# snc98_Display_15x7-Segment_3-digitDispla.net
KiCad netlist of a schematic drawn in EAGLE
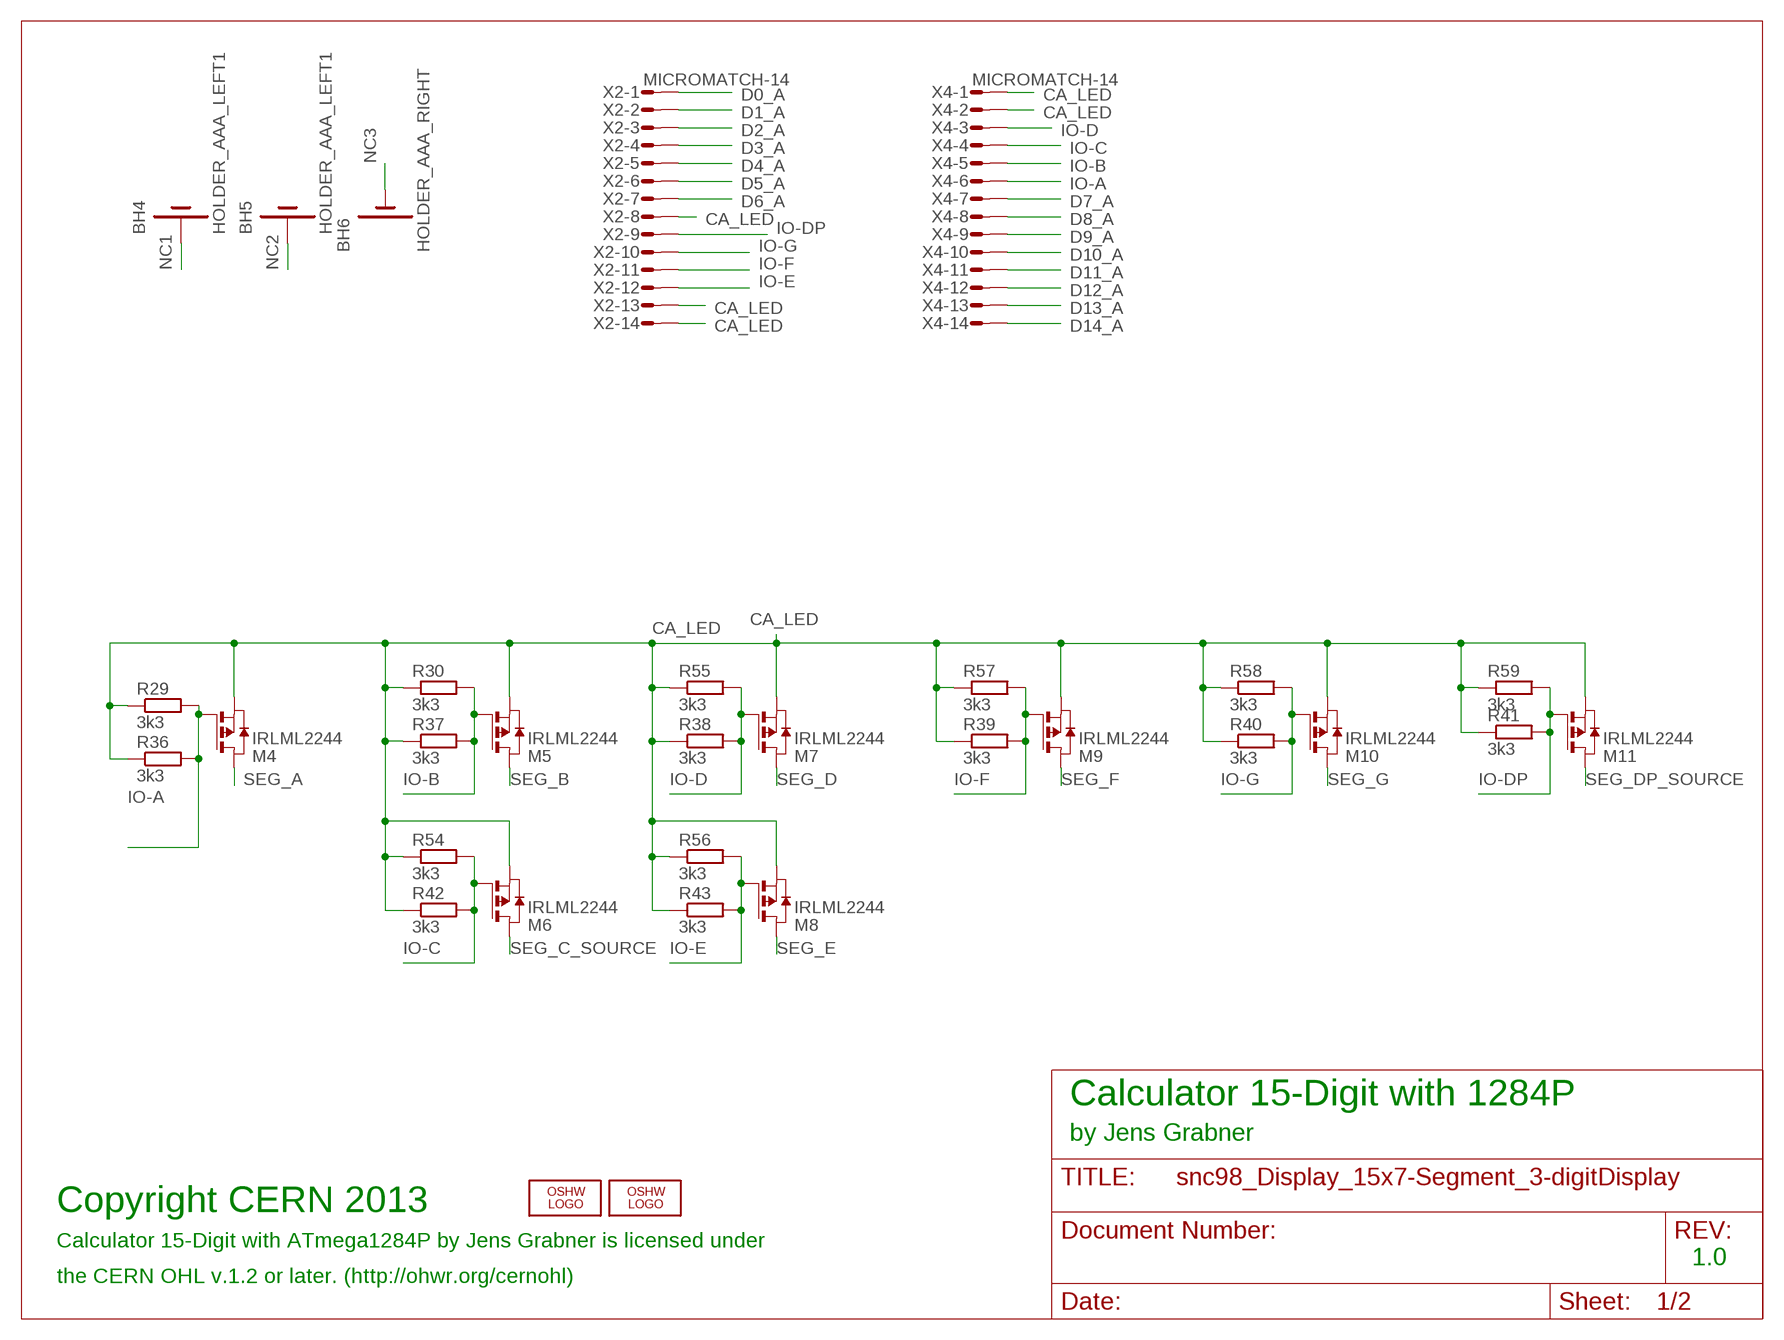
[diagram p0: schematic, sheet 1]
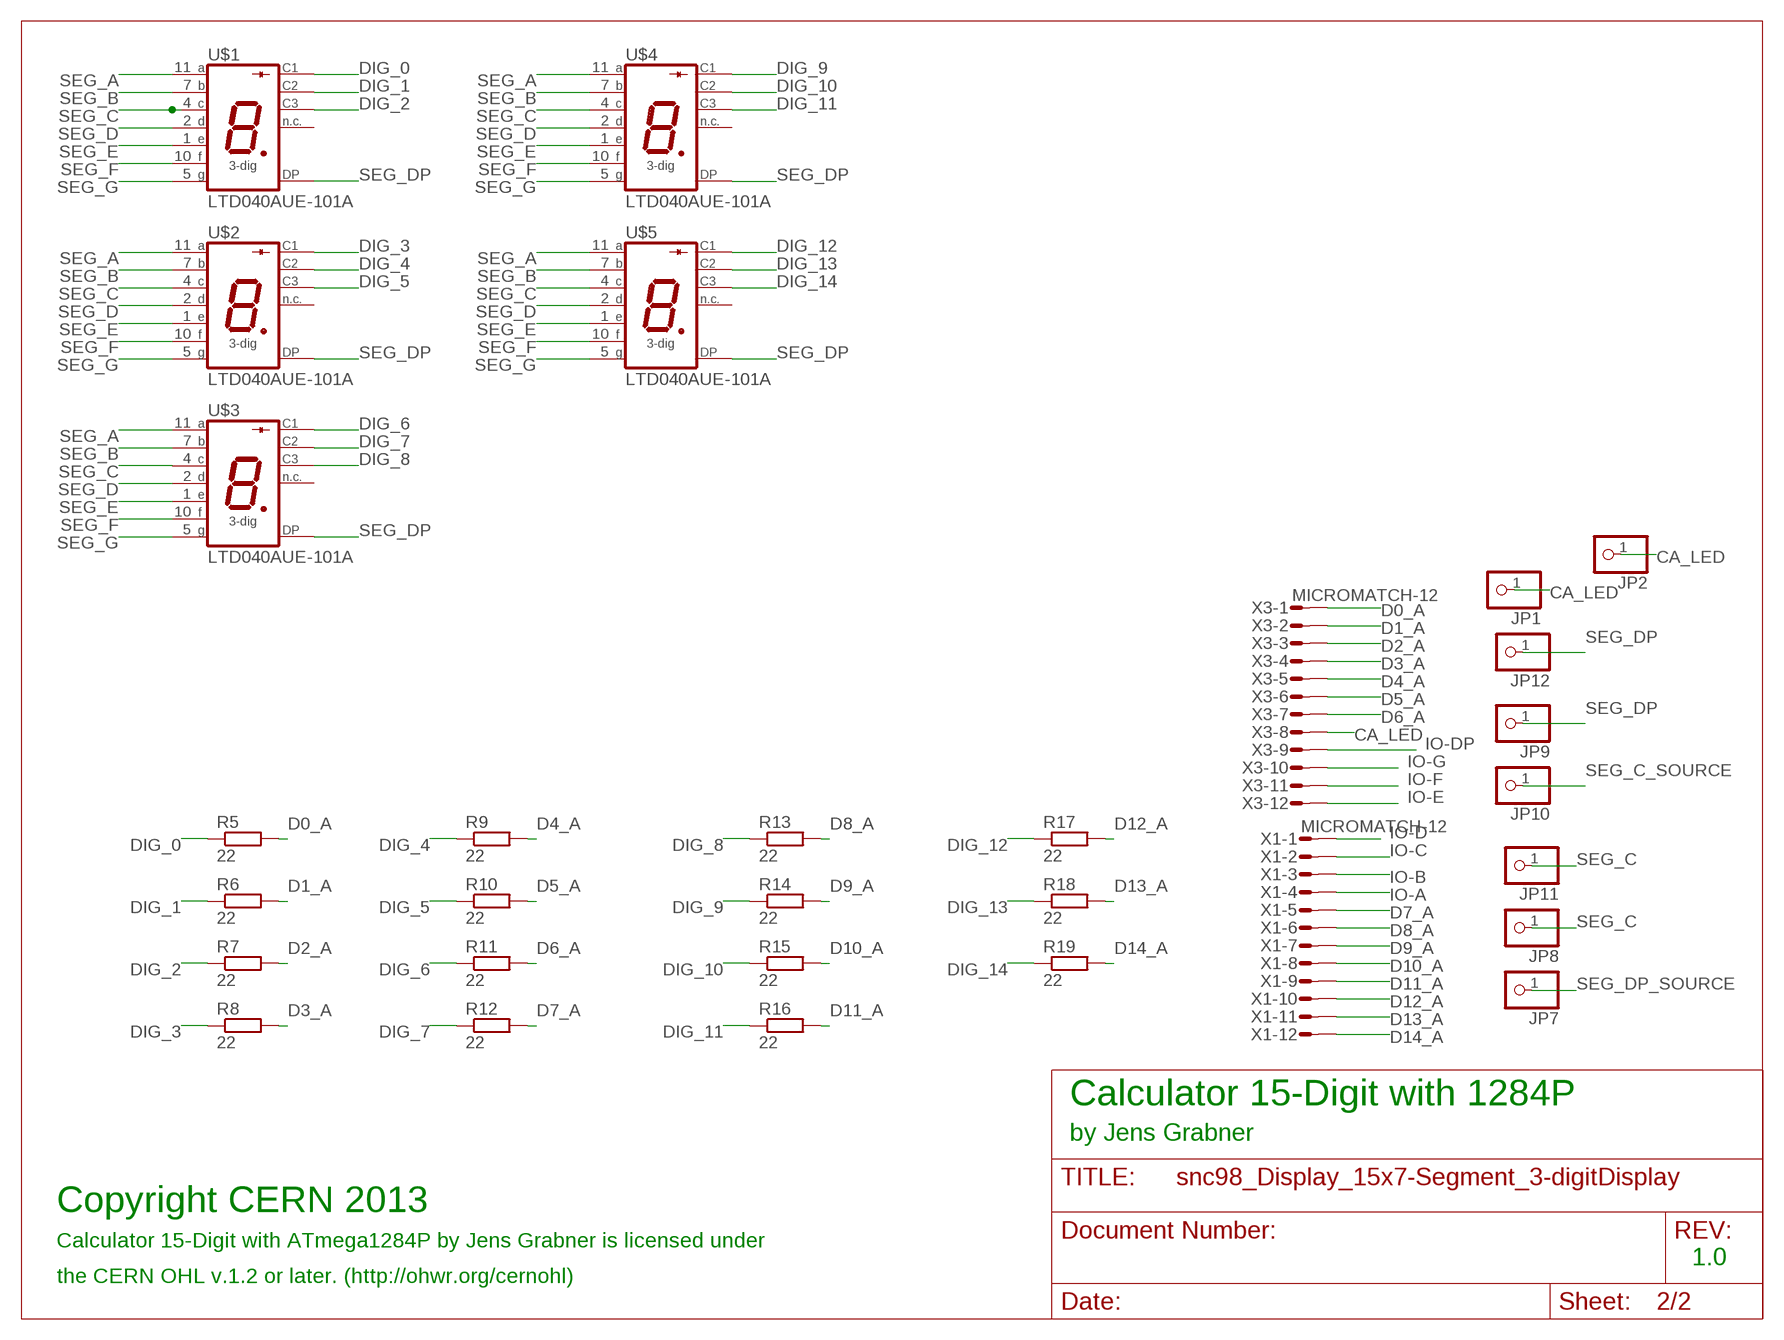
[diagram p1: schematic, sheet 2]

(export (version "E")
  (design (tool "Eeschema 10.0.6"))
  (components
    (comp (ref "JP1")
      (value "PINHD-1X1")
      (footprint "eagle-import:1X01")
      (libsource (lib "eagle-import") (part "PINHD-1X1"))
    )
    (comp (ref "JP2")
      (value "PINHD-1X1")
      (footprint "eagle-import:1X01")
      (libsource (lib "eagle-import") (part "PINHD-1X1"))
    )
    (comp (ref "JP7")
      (value "PINHD-1X1")
      (footprint "eagle-import:1X01")
      (libsource (lib "eagle-import") (part "PINHD-1X1"))
    )
    (comp (ref "JP8")
      (value "PINHD-1X1")
      (footprint "eagle-import:1X01")
      (libsource (lib "eagle-import") (part "PINHD-1X1"))
    )
    (comp (ref "JP9")
      (value "PINHD-1X1")
      (footprint "eagle-import:1X01")
      (libsource (lib "eagle-import") (part "PINHD-1X1"))
    )
    (comp (ref "JP10")
      (value "PINHD-1X1")
      (footprint "eagle-import:1X01")
      (libsource (lib "eagle-import") (part "PINHD-1X1"))
    )
    (comp (ref "JP11")
      (value "PINHD-1X1")
      (footprint "eagle-import:1X01")
      (libsource (lib "eagle-import") (part "PINHD-1X1"))
    )
    (comp (ref "JP12")
      (value "PINHD-1X1")
      (footprint "eagle-import:1X01")
      (libsource (lib "eagle-import") (part "PINHD-1X1"))
    )
    (comp (ref "R5")
      (value "22")
      (footprint "eagle-import:R1210")
      (libsource (lib "eagle-import") (part "R-EU_R1210"))
    )
    (comp (ref "R6")
      (value "22")
      (footprint "eagle-import:R1210")
      (libsource (lib "eagle-import") (part "R-EU_R1210"))
    )
    (comp (ref "R7")
      (value "22")
      (footprint "eagle-import:R1210")
      (libsource (lib "eagle-import") (part "R-EU_R1210"))
    )
    (comp (ref "R8")
      (value "22")
      (footprint "eagle-import:R1210")
      (libsource (lib "eagle-import") (part "R-EU_R1210"))
    )
    (comp (ref "R9")
      (value "22")
      (footprint "eagle-import:R1210")
      (libsource (lib "eagle-import") (part "R-EU_R1210"))
    )
    (comp (ref "R10")
      (value "22")
      (footprint "eagle-import:R1210")
      (libsource (lib "eagle-import") (part "R-EU_R1210"))
    )
    (comp (ref "R11")
      (value "22")
      (footprint "eagle-import:R1210")
      (libsource (lib "eagle-import") (part "R-EU_R1210"))
    )
    (comp (ref "R12")
      (value "22")
      (footprint "eagle-import:R1210")
      (libsource (lib "eagle-import") (part "R-EU_R1210"))
    )
    (comp (ref "R13")
      (value "22")
      (footprint "eagle-import:R1210")
      (libsource (lib "eagle-import") (part "R-EU_R1210"))
    )
    (comp (ref "R14")
      (value "22")
      (footprint "eagle-import:R1210")
      (libsource (lib "eagle-import") (part "R-EU_R1210"))
    )
    (comp (ref "R15")
      (value "22")
      (footprint "eagle-import:R1210")
      (libsource (lib "eagle-import") (part "R-EU_R1210"))
    )
    (comp (ref "R16")
      (value "22")
      (footprint "eagle-import:R1210")
      (libsource (lib "eagle-import") (part "R-EU_R1210"))
    )
    (comp (ref "R17")
      (value "22")
      (footprint "eagle-import:R1210")
      (libsource (lib "eagle-import") (part "R-EU_R1210"))
    )
    (comp (ref "R18")
      (value "22")
      (footprint "eagle-import:R1210")
      (libsource (lib "eagle-import") (part "R-EU_R1210"))
    )
    (comp (ref "R19")
      (value "22")
      (footprint "eagle-import:R1210")
      (libsource (lib "eagle-import") (part "R-EU_R1210"))
    )
    (comp (ref "U$1")
      (value "LTD040AUE-101A")
      (footprint "eagle-import:LTD040AUE-101A")
      (libsource (lib "eagle-import") (part "LTD040AUE-101A"))
    )
    (comp (ref "U$2")
      (value "LTD040AUE-101A")
      (footprint "eagle-import:LTD040AUE-101A")
      (libsource (lib "eagle-import") (part "LTD040AUE-101A"))
    )
    (comp (ref "U$3")
      (value "LTD040AUE-101A")
      (footprint "eagle-import:LTD040AUE-101A")
      (libsource (lib "eagle-import") (part "LTD040AUE-101A"))
    )
    (comp (ref "U$4")
      (value "LTD040AUE-101A")
      (footprint "eagle-import:LTD040AUE-101A")
      (libsource (lib "eagle-import") (part "LTD040AUE-101A"))
    )
    (comp (ref "U$5")
      (value "LTD040AUE-101A")
      (footprint "eagle-import:LTD040AUE-101A")
      (libsource (lib "eagle-import") (part "LTD040AUE-101A"))
    )
    (comp (ref "X1")
      (value "MICROMATCH-12")
      (footprint "eagle-import:MICROMATCH-12")
      (fields (field (name "MF") "FARNELL") (field (name "MPN") "8-215464-2"))
      (libsource (lib "eagle-import") (part "MICROMATCH-12"))
    )
    (comp (ref "X3")
      (value "MICROMATCH-12")
      (footprint "eagle-import:MICROMATCH-12")
      (fields (field (name "MF") "FARNELL") (field (name "MPN") "8-215464-2"))
      (libsource (lib "eagle-import") (part "MICROMATCH-12"))
    )
    (comp (ref "BH4")
      (value "HOLDER_AAA_LEFT1")
      (footprint "eagle-import:BATTERY-AAA-LEFT")
      (libsource (lib "eagle-import") (part "HOLDER_AAA_LEFT1"))
    )
    (comp (ref "BH5")
      (value "HOLDER_AAA_LEFT1")
      (footprint "eagle-import:BATTERY-AAA-LEFT")
      (libsource (lib "eagle-import") (part "HOLDER_AAA_LEFT1"))
    )
    (comp (ref "BH6")
      (value "HOLDER_AAA_RIGHT")
      (footprint "eagle-import:BATTERY-AAA-RIGHT")
      (libsource (lib "eagle-import") (part "HOLDER_AAA_RIGHT"))
    )
    (comp (ref "LOGO1")
      (value "OSHW_LOGO_8MILX0150-NT")
      (footprint "eagle-import:OSHW_8X150_NOTEXT")
      (libsource (lib "eagle-import") (part "OSHW_LOGO_8MILX0150-NT"))
    )
    (comp (ref "LOGO3")
      (value "OSHW_LOGO_6MILX0100-NT")
      (footprint "eagle-import:OSHW_6X100_NOTEXT")
      (libsource (lib "eagle-import") (part "OSHW_LOGO_6MILX0100-NT"))
    )
    (comp (ref "M4")
      (value "IRLML2244")
      (footprint "eagle-import:SOT-23")
      (libsource (lib "eagle-import") (part "IRLML6402"))
    )
    (comp (ref "M5")
      (value "IRLML2244")
      (footprint "eagle-import:SOT-23")
      (libsource (lib "eagle-import") (part "IRLML6402"))
    )
    (comp (ref "M6")
      (value "IRLML2244")
      (footprint "eagle-import:SOT-23")
      (libsource (lib "eagle-import") (part "IRLML6402"))
    )
    (comp (ref "M7")
      (value "IRLML2244")
      (footprint "eagle-import:SOT-23")
      (libsource (lib "eagle-import") (part "IRLML6402"))
    )
    (comp (ref "M8")
      (value "IRLML2244")
      (footprint "eagle-import:SOT-23")
      (libsource (lib "eagle-import") (part "IRLML6402"))
    )
    (comp (ref "M9")
      (value "IRLML2244")
      (footprint "eagle-import:SOT-23")
      (libsource (lib "eagle-import") (part "IRLML6402"))
    )
    (comp (ref "M10")
      (value "IRLML2244")
      (footprint "eagle-import:SOT-23")
      (libsource (lib "eagle-import") (part "IRLML6402"))
    )
    (comp (ref "M11")
      (value "IRLML2244")
      (footprint "eagle-import:SOT-23")
      (libsource (lib "eagle-import") (part "IRLML6402"))
    )
    (comp (ref "R29")
      (value "3k3")
      (footprint "eagle-import:0204_5")
      (libsource (lib "eagle-import") (part "R-EU_0204/5"))
    )
    (comp (ref "R30")
      (value "3k3")
      (footprint "eagle-import:0204_5")
      (libsource (lib "eagle-import") (part "R-EU_0204/5"))
    )
    (comp (ref "R36")
      (value "3k3")
      (footprint "eagle-import:R1206")
      (libsource (lib "eagle-import") (part "R-EU_R1206"))
    )
    (comp (ref "R37")
      (value "3k3")
      (footprint "eagle-import:R1206")
      (libsource (lib "eagle-import") (part "R-EU_R1206"))
    )
    (comp (ref "R38")
      (value "3k3")
      (footprint "eagle-import:R1206")
      (libsource (lib "eagle-import") (part "R-EU_R1206"))
    )
    (comp (ref "R39")
      (value "3k3")
      (footprint "eagle-import:R1206")
      (libsource (lib "eagle-import") (part "R-EU_R1206"))
    )
    (comp (ref "R40")
      (value "3k3")
      (footprint "eagle-import:R1206")
      (libsource (lib "eagle-import") (part "R-EU_R1206"))
    )
    (comp (ref "R41")
      (value "3k3")
      (footprint "eagle-import:R1206")
      (libsource (lib "eagle-import") (part "R-EU_R1206"))
    )
    (comp (ref "R42")
      (value "3k3")
      (footprint "eagle-import:R1206")
      (libsource (lib "eagle-import") (part "R-EU_R1206"))
    )
    (comp (ref "R43")
      (value "3k3")
      (footprint "eagle-import:R1206")
      (libsource (lib "eagle-import") (part "R-EU_R1206"))
    )
    (comp (ref "R54")
      (value "3k3")
      (footprint "eagle-import:0204_5")
      (libsource (lib "eagle-import") (part "R-EU_0204/5"))
    )
    (comp (ref "R55")
      (value "3k3")
      (footprint "eagle-import:0204_5")
      (libsource (lib "eagle-import") (part "R-EU_0204/5"))
    )
    (comp (ref "R56")
      (value "3k3")
      (footprint "eagle-import:0204_5")
      (libsource (lib "eagle-import") (part "R-EU_0204/5"))
    )
    (comp (ref "R57")
      (value "3k3")
      (footprint "eagle-import:0204_5")
      (libsource (lib "eagle-import") (part "R-EU_0204/5"))
    )
    (comp (ref "R58")
      (value "3k3")
      (footprint "eagle-import:0204_5")
      (libsource (lib "eagle-import") (part "R-EU_0204/5"))
    )
    (comp (ref "R59")
      (value "3k3")
      (footprint "eagle-import:0204_5")
      (libsource (lib "eagle-import") (part "R-EU_0204/5"))
    )
    (comp (ref "X2")
      (value "MICROMATCH-14")
      (footprint "eagle-import:MICROMATCH-14")
      (fields (field (name "MF") "FARNELL") (field (name "MPN") "8-215464-4"))
      (libsource (lib "eagle-import") (part "MICROMATCH-14"))
    )
    (comp (ref "X4")
      (value "MICROMATCH-14")
      (footprint "eagle-import:MICROMATCH-14")
      (fields (field (name "MF") "FARNELL") (field (name "MPN") "8-215464-4"))
      (libsource (lib "eagle-import") (part "MICROMATCH-14"))
    )
  )
  (nets
    (net (code "1") (name "CA_LED") (class "Default")
      (node (ref "JP1") (pin "1") (pinfunction "1_1") (pintype "passive"))
      (node (ref "JP2") (pin "1") (pinfunction "1_1") (pintype "passive"))
      (node (ref "M10") (pin "2") (pinfunction "S_2") (pintype "passive"))
      (node (ref "M11") (pin "2") (pinfunction "S_2") (pintype "passive"))
      (node (ref "M4") (pin "2") (pinfunction "S_2") (pintype "passive"))
      (node (ref "M5") (pin "2") (pinfunction "S_2") (pintype "passive"))
      (node (ref "M6") (pin "2") (pinfunction "S_2") (pintype "passive"))
      (node (ref "M7") (pin "2") (pinfunction "S_2") (pintype "passive"))
      (node (ref "M8") (pin "2") (pinfunction "S_2") (pintype "passive"))
      (node (ref "M9") (pin "2") (pinfunction "S_2") (pintype "passive"))
      (node (ref "R29") (pin "1") (pinfunction "1_1") (pintype "passive"))
      (node (ref "R30") (pin "1") (pinfunction "1_1") (pintype "passive"))
      (node (ref "R36") (pin "1") (pinfunction "1_1") (pintype "passive"))
      (node (ref "R37") (pin "1") (pinfunction "1_1") (pintype "passive"))
      (node (ref "R38") (pin "1") (pinfunction "1_1") (pintype "passive"))
      (node (ref "R39") (pin "1") (pinfunction "1_1") (pintype "passive"))
      (node (ref "R40") (pin "1") (pinfunction "1_1") (pintype "passive"))
      (node (ref "R41") (pin "1") (pinfunction "1_1") (pintype "passive"))
      (node (ref "R42") (pin "1") (pinfunction "1_1") (pintype "passive"))
      (node (ref "R43") (pin "1") (pinfunction "1_1") (pintype "passive"))
      (node (ref "R54") (pin "1") (pinfunction "1_1") (pintype "passive"))
      (node (ref "R55") (pin "1") (pinfunction "1_1") (pintype "passive"))
      (node (ref "R56") (pin "1") (pinfunction "1_1") (pintype "passive"))
      (node (ref "R57") (pin "1") (pinfunction "1_1") (pintype "passive"))
      (node (ref "R58") (pin "1") (pinfunction "1_1") (pintype "passive"))
      (node (ref "R59") (pin "1") (pinfunction "1_1") (pintype "passive"))
      (node (ref "X2") (pin "13") (pinfunction "S_13") (pintype "passive"))
      (node (ref "X2") (pin "14") (pinfunction "S_14") (pintype "passive"))
      (node (ref "X2") (pin "8") (pinfunction "S_8") (pintype "passive"))
      (node (ref "X3") (pin "8") (pinfunction "S_8") (pintype "passive"))
      (node (ref "X4") (pin "1") (pinfunction "S_1") (pintype "passive"))
      (node (ref "X4") (pin "2") (pinfunction "S_2") (pintype "passive"))
    )
    (net (code "2") (name "D0_A") (class "Default")
      (node (ref "R5") (pin "2") (pinfunction "2_2") (pintype "passive"))
      (node (ref "X2") (pin "1") (pinfunction "S_1") (pintype "passive"))
      (node (ref "X3") (pin "1") (pinfunction "S_1") (pintype "passive"))
    )
    (net (code "3") (name "D1_A") (class "Default")
      (node (ref "R6") (pin "2") (pinfunction "2_2") (pintype "passive"))
      (node (ref "X2") (pin "2") (pinfunction "S_2") (pintype "passive"))
      (node (ref "X3") (pin "2") (pinfunction "S_2") (pintype "passive"))
    )
    (net (code "4") (name "D2_A") (class "Default")
      (node (ref "R7") (pin "2") (pinfunction "2_2") (pintype "passive"))
      (node (ref "X2") (pin "3") (pinfunction "S_3") (pintype "passive"))
      (node (ref "X3") (pin "3") (pinfunction "S_3") (pintype "passive"))
    )
    (net (code "5") (name "D3_A") (class "Default")
      (node (ref "R8") (pin "2") (pinfunction "2_2") (pintype "passive"))
      (node (ref "X2") (pin "4") (pinfunction "S_4") (pintype "passive"))
      (node (ref "X3") (pin "4") (pinfunction "S_4") (pintype "passive"))
    )
    (net (code "6") (name "D4_A") (class "Default")
      (node (ref "R9") (pin "2") (pinfunction "2_2") (pintype "passive"))
      (node (ref "X2") (pin "5") (pinfunction "S_5") (pintype "passive"))
      (node (ref "X3") (pin "5") (pinfunction "S_5") (pintype "passive"))
    )
    (net (code "7") (name "D5_A") (class "Default")
      (node (ref "R10") (pin "2") (pinfunction "2_2") (pintype "passive"))
      (node (ref "X2") (pin "6") (pinfunction "S_6") (pintype "passive"))
      (node (ref "X3") (pin "6") (pinfunction "S_6") (pintype "passive"))
    )
    (net (code "8") (name "D6_A") (class "Default")
      (node (ref "R11") (pin "2") (pinfunction "2_2") (pintype "passive"))
      (node (ref "X2") (pin "7") (pinfunction "S_7") (pintype "passive"))
      (node (ref "X3") (pin "7") (pinfunction "S_7") (pintype "passive"))
    )
    (net (code "9") (name "D7_A") (class "Default")
      (node (ref "R12") (pin "2") (pinfunction "2_2") (pintype "passive"))
      (node (ref "X1") (pin "5") (pinfunction "S_5") (pintype "passive"))
      (node (ref "X4") (pin "7") (pinfunction "S_7") (pintype "passive"))
    )
    (net (code "10") (name "D8_A") (class "Default")
      (node (ref "R13") (pin "2") (pinfunction "2_2") (pintype "passive"))
      (node (ref "X1") (pin "6") (pinfunction "S_6") (pintype "passive"))
      (node (ref "X4") (pin "8") (pinfunction "S_8") (pintype "passive"))
    )
    (net (code "11") (name "D9_A") (class "Default")
      (node (ref "R14") (pin "2") (pinfunction "2_2") (pintype "passive"))
      (node (ref "X1") (pin "7") (pinfunction "S_7") (pintype "passive"))
      (node (ref "X4") (pin "9") (pinfunction "S_9") (pintype "passive"))
    )
    (net (code "12") (name "D10_A") (class "Default")
      (node (ref "R15") (pin "2") (pinfunction "2_2") (pintype "passive"))
      (node (ref "X1") (pin "8") (pinfunction "S_8") (pintype "passive"))
      (node (ref "X4") (pin "10") (pinfunction "S_10") (pintype "passive"))
    )
    (net (code "13") (name "D11_A") (class "Default")
      (node (ref "R16") (pin "2") (pinfunction "2_2") (pintype "passive"))
      (node (ref "X1") (pin "9") (pinfunction "S_9") (pintype "passive"))
      (node (ref "X4") (pin "11") (pinfunction "S_11") (pintype "passive"))
    )
    (net (code "14") (name "D12_A") (class "Default")
      (node (ref "R17") (pin "2") (pinfunction "2_2") (pintype "passive"))
      (node (ref "X1") (pin "10") (pinfunction "S_10") (pintype "passive"))
      (node (ref "X4") (pin "12") (pinfunction "S_12") (pintype "passive"))
    )
    (net (code "15") (name "D13_A") (class "Default")
      (node (ref "R18") (pin "2") (pinfunction "2_2") (pintype "passive"))
      (node (ref "X1") (pin "11") (pinfunction "S_11") (pintype "passive"))
      (node (ref "X4") (pin "13") (pinfunction "S_13") (pintype "passive"))
    )
    (net (code "16") (name "D14_A") (class "Default")
      (node (ref "R19") (pin "2") (pinfunction "2_2") (pintype "passive"))
      (node (ref "X1") (pin "12") (pinfunction "S_12") (pintype "passive"))
      (node (ref "X4") (pin "14") (pinfunction "S_14") (pintype "passive"))
    )
    (net (code "17") (name "DIG_0") (class "Default")
      (node (ref "R5") (pin "1") (pinfunction "1_1") (pintype "passive"))
      (node (ref "U$1") (pin "12") (pinfunction "C1_12") (pintype "passive"))
    )
    (net (code "18") (name "DIG_1") (class "Default")
      (node (ref "R6") (pin "1") (pinfunction "1_1") (pintype "passive"))
      (node (ref "U$1") (pin "9") (pinfunction "C2_9") (pintype "passive"))
    )
    (net (code "19") (name "DIG_2") (class "Default")
      (node (ref "R7") (pin "1") (pinfunction "1_1") (pintype "passive"))
      (node (ref "U$1") (pin "8") (pinfunction "C3_8") (pintype "passive"))
    )
    (net (code "20") (name "DIG_3") (class "Default")
      (node (ref "R8") (pin "1") (pinfunction "1_1") (pintype "passive"))
      (node (ref "U$2") (pin "12") (pinfunction "C1_12") (pintype "passive"))
    )
    (net (code "21") (name "DIG_4") (class "Default")
      (node (ref "R9") (pin "1") (pinfunction "1_1") (pintype "passive"))
      (node (ref "U$2") (pin "9") (pinfunction "C2_9") (pintype "passive"))
    )
    (net (code "22") (name "DIG_5") (class "Default")
      (node (ref "R10") (pin "1") (pinfunction "1_1") (pintype "passive"))
      (node (ref "U$2") (pin "8") (pinfunction "C3_8") (pintype "passive"))
    )
    (net (code "23") (name "DIG_6") (class "Default")
      (node (ref "R11") (pin "1") (pinfunction "1_1") (pintype "passive"))
      (node (ref "U$3") (pin "12") (pinfunction "C1_12") (pintype "passive"))
    )
    (net (code "24") (name "DIG_7") (class "Default")
      (node (ref "R12") (pin "1") (pinfunction "1_1") (pintype "passive"))
      (node (ref "U$3") (pin "9") (pinfunction "C2_9") (pintype "passive"))
    )
    (net (code "25") (name "DIG_8") (class "Default")
      (node (ref "R13") (pin "1") (pinfunction "1_1") (pintype "passive"))
      (node (ref "U$3") (pin "8") (pinfunction "C3_8") (pintype "passive"))
    )
    (net (code "26") (name "DIG_9") (class "Default")
      (node (ref "R14") (pin "1") (pinfunction "1_1") (pintype "passive"))
      (node (ref "U$4") (pin "12") (pinfunction "C1_12") (pintype "passive"))
    )
    (net (code "27") (name "DIG_10") (class "Default")
      (node (ref "R15") (pin "1") (pinfunction "1_1") (pintype "passive"))
      (node (ref "U$4") (pin "9") (pinfunction "C2_9") (pintype "passive"))
    )
    (net (code "28") (name "DIG_11") (class "Default")
      (node (ref "R16") (pin "1") (pinfunction "1_1") (pintype "passive"))
      (node (ref "U$4") (pin "8") (pinfunction "C3_8") (pintype "passive"))
    )
    (net (code "29") (name "DIG_12") (class "Default")
      (node (ref "R17") (pin "1") (pinfunction "1_1") (pintype "passive"))
      (node (ref "U$5") (pin "12") (pinfunction "C1_12") (pintype "passive"))
    )
    (net (code "30") (name "DIG_13") (class "Default")
      (node (ref "R18") (pin "1") (pinfunction "1_1") (pintype "passive"))
      (node (ref "U$5") (pin "9") (pinfunction "C2_9") (pintype "passive"))
    )
    (net (code "31") (name "DIG_14") (class "Default")
      (node (ref "R19") (pin "1") (pinfunction "1_1") (pintype "passive"))
      (node (ref "U$5") (pin "8") (pinfunction "C3_8") (pintype "passive"))
    )
    (net (code "32") (name "IO-A") (class "Default")
      (node (ref "M4") (pin "1") (pinfunction "G_1") (pintype "passive"))
      (node (ref "R29") (pin "2") (pinfunction "2_2") (pintype "passive"))
      (node (ref "R36") (pin "2") (pinfunction "2_2") (pintype "passive"))
      (node (ref "X1") (pin "4") (pinfunction "S_4") (pintype "passive"))
      (node (ref "X4") (pin "6") (pinfunction "S_6") (pintype "passive"))
    )
    (net (code "33") (name "IO-B") (class "Default")
      (node (ref "M5") (pin "1") (pinfunction "G_1") (pintype "passive"))
      (node (ref "R30") (pin "2") (pinfunction "2_2") (pintype "passive"))
      (node (ref "R37") (pin "2") (pinfunction "2_2") (pintype "passive"))
      (node (ref "X1") (pin "3") (pinfunction "S_3") (pintype "passive"))
      (node (ref "X4") (pin "5") (pinfunction "S_5") (pintype "passive"))
    )
    (net (code "34") (name "IO-C") (class "Default")
      (node (ref "M6") (pin "1") (pinfunction "G_1") (pintype "passive"))
      (node (ref "R42") (pin "2") (pinfunction "2_2") (pintype "passive"))
      (node (ref "R54") (pin "2") (pinfunction "2_2") (pintype "passive"))
      (node (ref "X1") (pin "2") (pinfunction "S_2") (pintype "passive"))
      (node (ref "X4") (pin "4") (pinfunction "S_4") (pintype "passive"))
    )
    (net (code "35") (name "IO-D") (class "Default")
      (node (ref "M7") (pin "1") (pinfunction "G_1") (pintype "passive"))
      (node (ref "R38") (pin "2") (pinfunction "2_2") (pintype "passive"))
      (node (ref "R55") (pin "2") (pinfunction "2_2") (pintype "passive"))
      (node (ref "X1") (pin "1") (pinfunction "S_1") (pintype "passive"))
      (node (ref "X4") (pin "3") (pinfunction "S_3") (pintype "passive"))
    )
    (net (code "36") (name "IO-DP") (class "Default")
      (node (ref "M11") (pin "1") (pinfunction "G_1") (pintype "passive"))
      (node (ref "R41") (pin "2") (pinfunction "2_2") (pintype "passive"))
      (node (ref "R59") (pin "2") (pinfunction "2_2") (pintype "passive"))
      (node (ref "X2") (pin "9") (pinfunction "S_9") (pintype "passive"))
      (node (ref "X3") (pin "9") (pinfunction "S_9") (pintype "passive"))
    )
    (net (code "37") (name "IO-E") (class "Default")
      (node (ref "M8") (pin "1") (pinfunction "G_1") (pintype "passive"))
      (node (ref "R43") (pin "2") (pinfunction "2_2") (pintype "passive"))
      (node (ref "R56") (pin "2") (pinfunction "2_2") (pintype "passive"))
      (node (ref "X2") (pin "12") (pinfunction "S_12") (pintype "passive"))
      (node (ref "X3") (pin "12") (pinfunction "S_12") (pintype "passive"))
    )
    (net (code "38") (name "IO-F") (class "Default")
      (node (ref "M9") (pin "1") (pinfunction "G_1") (pintype "passive"))
      (node (ref "R39") (pin "2") (pinfunction "2_2") (pintype "passive"))
      (node (ref "R57") (pin "2") (pinfunction "2_2") (pintype "passive"))
      (node (ref "X2") (pin "11") (pinfunction "S_11") (pintype "passive"))
      (node (ref "X3") (pin "11") (pinfunction "S_11") (pintype "passive"))
    )
    (net (code "39") (name "IO-G") (class "Default")
      (node (ref "M10") (pin "1") (pinfunction "G_1") (pintype "passive"))
      (node (ref "R40") (pin "2") (pinfunction "2_2") (pintype "passive"))
      (node (ref "R58") (pin "2") (pinfunction "2_2") (pintype "passive"))
      (node (ref "X2") (pin "10") (pinfunction "S_10") (pintype "passive"))
      (node (ref "X3") (pin "10") (pinfunction "S_10") (pintype "passive"))
    )
    (net (code "40") (name "NC1") (class "Default")
      (node (ref "BH4") (pin "P1") (pinfunction "+_P1") (pintype "power_in"))
      (node (ref "BH4") (pin "P2") (pinfunction "+_P2") (pintype "power_in"))
      (node (ref "BH4") (pin "P3") (pinfunction "+_P3") (pintype "power_in"))
      (node (ref "BH4") (pin "P4") (pinfunction "+_P4") (pintype "power_in"))
    )
    (net (code "41") (name "NC2") (class "Default")
      (node (ref "BH5") (pin "P1") (pinfunction "+_P1") (pintype "power_in"))
      (node (ref "BH5") (pin "P2") (pinfunction "+_P2") (pintype "power_in"))
      (node (ref "BH5") (pin "P3") (pinfunction "+_P3") (pintype "power_in"))
      (node (ref "BH5") (pin "P4") (pinfunction "+_P4") (pintype "power_in"))
    )
    (net (code "42") (name "NC3") (class "Default")
      (node (ref "BH6") (pin "M1") (pinfunction "-_M1") (pintype "power_in"))
      (node (ref "BH6") (pin "M2") (pinfunction "-_M2") (pintype "power_in"))
      (node (ref "BH6") (pin "M3") (pinfunction "-_M3") (pintype "power_in"))
      (node (ref "BH6") (pin "M4") (pinfunction "-_M4") (pintype "power_in"))
    )
    (net (code "43") (name "SEG_A") (class "Default")
      (node (ref "M4") (pin "3") (pinfunction "D_3") (pintype "passive"))
      (node (ref "U$1") (pin "11") (pinfunction "A_11") (pintype "passive"))
      (node (ref "U$2") (pin "11") (pinfunction "A_11") (pintype "passive"))
      (node (ref "U$3") (pin "11") (pinfunction "A_11") (pintype "passive"))
      (node (ref "U$4") (pin "11") (pinfunction "A_11") (pintype "passive"))
      (node (ref "U$5") (pin "11") (pinfunction "A_11") (pintype "passive"))
    )
    (net (code "44") (name "SEG_B") (class "Default")
      (node (ref "M5") (pin "3") (pinfunction "D_3") (pintype "passive"))
      (node (ref "U$1") (pin "7") (pinfunction "B_7") (pintype "passive"))
      (node (ref "U$2") (pin "7") (pinfunction "B_7") (pintype "passive"))
      (node (ref "U$3") (pin "7") (pinfunction "B_7") (pintype "passive"))
      (node (ref "U$4") (pin "7") (pinfunction "B_7") (pintype "passive"))
      (node (ref "U$5") (pin "7") (pinfunction "B_7") (pintype "passive"))
    )
    (net (code "45") (name "SEG_C") (class "Default")
      (node (ref "JP11") (pin "1") (pinfunction "1_1") (pintype "passive"))
      (node (ref "JP8") (pin "1") (pinfunction "1_1") (pintype "passive"))
      (node (ref "U$1") (pin "4") (pinfunction "C_4") (pintype "passive"))
      (node (ref "U$2") (pin "4") (pinfunction "C_4") (pintype "passive"))
      (node (ref "U$3") (pin "4") (pinfunction "C_4") (pintype "passive"))
      (node (ref "U$4") (pin "4") (pinfunction "C_4") (pintype "passive"))
      (node (ref "U$5") (pin "4") (pinfunction "C_4") (pintype "passive"))
    )
    (net (code "46") (name "SEG_C_SOURCE") (class "Default")
      (node (ref "JP10") (pin "1") (pinfunction "1_1") (pintype "passive"))
      (node (ref "M6") (pin "3") (pinfunction "D_3") (pintype "passive"))
    )
    (net (code "47") (name "SEG_D") (class "Default")
      (node (ref "M7") (pin "3") (pinfunction "D_3") (pintype "passive"))
      (node (ref "U$1") (pin "2") (pinfunction "D_2") (pintype "passive"))
      (node (ref "U$2") (pin "2") (pinfunction "D_2") (pintype "passive"))
      (node (ref "U$3") (pin "2") (pinfunction "D_2") (pintype "passive"))
      (node (ref "U$4") (pin "2") (pinfunction "D_2") (pintype "passive"))
      (node (ref "U$5") (pin "2") (pinfunction "D_2") (pintype "passive"))
    )
    (net (code "48") (name "SEG_DP") (class "Default")
      (node (ref "JP12") (pin "1") (pinfunction "1_1") (pintype "passive"))
      (node (ref "JP9") (pin "1") (pinfunction "1_1") (pintype "passive"))
      (node (ref "U$1") (pin "3") (pinfunction "DP_3") (pintype "passive"))
      (node (ref "U$2") (pin "3") (pinfunction "DP_3") (pintype "passive"))
      (node (ref "U$3") (pin "3") (pinfunction "DP_3") (pintype "passive"))
      (node (ref "U$4") (pin "3") (pinfunction "DP_3") (pintype "passive"))
      (node (ref "U$5") (pin "3") (pinfunction "DP_3") (pintype "passive"))
    )
    (net (code "49") (name "SEG_DP_SOURCE") (class "Default")
      (node (ref "JP7") (pin "1") (pinfunction "1_1") (pintype "passive"))
      (node (ref "M11") (pin "3") (pinfunction "D_3") (pintype "passive"))
    )
    (net (code "50") (name "SEG_E") (class "Default")
      (node (ref "M8") (pin "3") (pinfunction "D_3") (pintype "passive"))
      (node (ref "U$1") (pin "1") (pinfunction "E_1") (pintype "passive"))
      (node (ref "U$2") (pin "1") (pinfunction "E_1") (pintype "passive"))
      (node (ref "U$3") (pin "1") (pinfunction "E_1") (pintype "passive"))
      (node (ref "U$4") (pin "1") (pinfunction "E_1") (pintype "passive"))
      (node (ref "U$5") (pin "1") (pinfunction "E_1") (pintype "passive"))
    )
    (net (code "51") (name "SEG_F") (class "Default")
      (node (ref "M9") (pin "3") (pinfunction "D_3") (pintype "passive"))
      (node (ref "U$1") (pin "10") (pinfunction "F_10") (pintype "passive"))
      (node (ref "U$2") (pin "10") (pinfunction "F_10") (pintype "passive"))
      (node (ref "U$3") (pin "10") (pinfunction "F_10") (pintype "passive"))
      (node (ref "U$4") (pin "10") (pinfunction "F_10") (pintype "passive"))
      (node (ref "U$5") (pin "10") (pinfunction "F_10") (pintype "passive"))
    )
    (net (code "52") (name "SEG_G") (class "Default")
      (node (ref "M10") (pin "3") (pinfunction "D_3") (pintype "passive"))
      (node (ref "U$1") (pin "5") (pinfunction "G_5") (pintype "passive"))
      (node (ref "U$2") (pin "5") (pinfunction "G_5") (pintype "passive"))
      (node (ref "U$3") (pin "5") (pinfunction "G_5") (pintype "passive"))
      (node (ref "U$4") (pin "5") (pinfunction "G_5") (pintype "passive"))
      (node (ref "U$5") (pin "5") (pinfunction "G_5") (pintype "passive"))
    )
    (net (code "53") (name "unconnected-(U$1-P$1-Pad6)") (class "Default")
      (node (ref "U$1") (pin "6") (pinfunction "P$1_6") (pintype "passive"))
    )
    (net (code "54") (name "unconnected-(U$2-P$1-Pad6)") (class "Default")
      (node (ref "U$2") (pin "6") (pinfunction "P$1_6") (pintype "passive"))
    )
    (net (code "55") (name "unconnected-(U$3-P$1-Pad6)") (class "Default")
      (node (ref "U$3") (pin "6") (pinfunction "P$1_6") (pintype "passive"))
    )
    (net (code "56") (name "unconnected-(U$4-P$1-Pad6)") (class "Default")
      (node (ref "U$4") (pin "6") (pinfunction "P$1_6") (pintype "passive"))
    )
    (net (code "57") (name "unconnected-(U$5-P$1-Pad6)") (class "Default")
      (node (ref "U$5") (pin "6") (pinfunction "P$1_6") (pintype "passive"))
    )
  )
)
